# encoder-seed.net
KiCad netlist of a schematic drawn in EAGLE
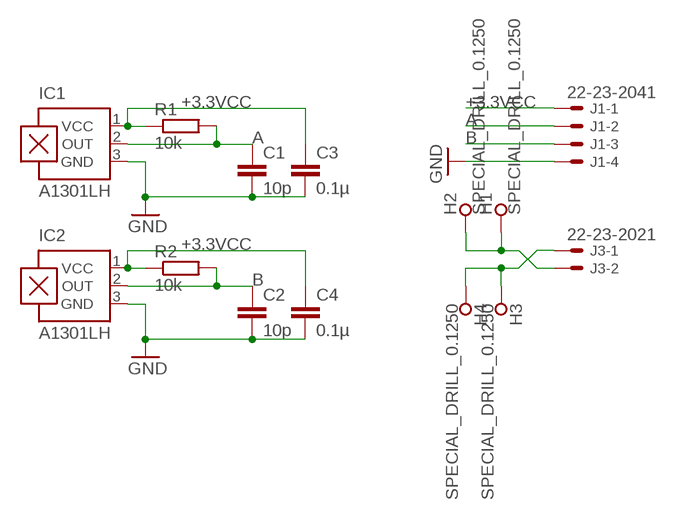
[diagram p0: schematic, sheet 1]

(export (version "E")
  (design (tool "Eeschema 10.0.6"))
  (components
    (comp (ref "C1")
      (value "10p")
      (footprint "eagle-import:C0805")
      (libsource (lib "eagle-import") (part "C-EUC0805"))
    )
    (comp (ref "C2")
      (value "10p")
      (footprint "eagle-import:C0805")
      (libsource (lib "eagle-import") (part "C-EUC0805"))
    )
    (comp (ref "C3")
      (value "0.1µ")
      (footprint "eagle-import:C0805")
      (libsource (lib "eagle-import") (part "C-EUC0805"))
    )
    (comp (ref "C4")
      (value "0.1µ")
      (footprint "eagle-import:C0805")
      (libsource (lib "eagle-import") (part "C-EUC0805"))
    )
    (comp (ref "H1")
      (value "SPECIAL_DRILL_0.1250")
      (footprint "eagle-import:PAD_0.1250")
      (libsource (lib "eagle-import") (part "SPECIAL_DRILL_0.1250"))
    )
    (comp (ref "H2")
      (value "SPECIAL_DRILL_0.1250")
      (footprint "eagle-import:PAD_0.1250")
      (libsource (lib "eagle-import") (part "SPECIAL_DRILL_0.1250"))
    )
    (comp (ref "H3")
      (value "SPECIAL_DRILL_0.1250")
      (footprint "eagle-import:PAD_0.1250")
      (libsource (lib "eagle-import") (part "SPECIAL_DRILL_0.1250"))
    )
    (comp (ref "H4")
      (value "SPECIAL_DRILL_0.1250")
      (footprint "eagle-import:PAD_0.1250")
      (libsource (lib "eagle-import") (part "SPECIAL_DRILL_0.1250"))
    )
    (comp (ref "IC1")
      (value "A1301LH")
      (footprint "eagle-import:SOT23-W")
      (fields (field (name "MF") "ALLEGRO MICROSYSTEMS, INC.") (field (name "MPN") "A1301ELHLT-T"))
      (libsource (lib "eagle-import") (part "A13?LH01"))
    )
    (comp (ref "IC2")
      (value "A1301LH")
      (footprint "eagle-import:SOT23-W")
      (fields (field (name "MF") "ALLEGRO MICROSYSTEMS, INC.") (field (name "MPN") "A1301ELHLT-T"))
      (libsource (lib "eagle-import") (part "A13?LH01"))
    )
    (comp (ref "J1")
      (value "22-23-2041")
      (footprint "eagle-import:22-23-2041")
      (fields (field (name "MF") "MOLEX"))
      (libsource (lib "eagle-import") (part "22-23-2041"))
    )
    (comp (ref "J3")
      (value "22-23-2021")
      (footprint "eagle-import:22-23-2021")
      (fields (field (name "MF") "MOLEX"))
      (libsource (lib "eagle-import") (part "22-23-2021"))
    )
    (comp (ref "R1")
      (value "10k")
      (footprint "eagle-import:R0805")
      (libsource (lib "eagle-import") (part "R-EU_R0805"))
    )
    (comp (ref "R2")
      (value "10k")
      (footprint "eagle-import:R0805")
      (libsource (lib "eagle-import") (part "R-EU_R0805"))
    )
  )
  (nets
    (net (code "1") (name "/+3.3VCC") (class "Default")
      (node (ref "C3") (pin "1") (pinfunction "1_1") (pintype "passive"))
      (node (ref "C4") (pin "1") (pinfunction "1_1") (pintype "passive"))
      (node (ref "IC1") (pin "1") (pinfunction "VCC_1") (pintype "power_in"))
      (node (ref "IC2") (pin "1") (pinfunction "VCC_1") (pintype "power_in"))
      (node (ref "J1") (pin "1") (pinfunction "S_1") (pintype "passive"))
      (node (ref "R1") (pin "1") (pinfunction "1_1") (pintype "passive"))
      (node (ref "R2") (pin "1") (pinfunction "1_1") (pintype "passive"))
    )
    (net (code "2") (name "/A") (class "Default")
      (node (ref "C1") (pin "1") (pinfunction "1_1") (pintype "passive"))
      (node (ref "IC1") (pin "2") (pinfunction "OUT_2") (pintype "output"))
      (node (ref "J1") (pin "2") (pinfunction "S_2") (pintype "passive"))
      (node (ref "R1") (pin "2") (pinfunction "2_2") (pintype "passive"))
    )
    (net (code "3") (name "/B") (class "Default")
      (node (ref "C2") (pin "1") (pinfunction "1_1") (pintype "passive"))
      (node (ref "IC2") (pin "2") (pinfunction "OUT_2") (pintype "output"))
      (node (ref "J1") (pin "3") (pinfunction "S_3") (pintype "passive"))
      (node (ref "R2") (pin "2") (pinfunction "2_2") (pintype "passive"))
    )
    (net (code "4") (name "GND") (class "Default")
      (node (ref "C1") (pin "2") (pinfunction "2_2") (pintype "passive"))
      (node (ref "C2") (pin "2") (pinfunction "2_2") (pintype "passive"))
      (node (ref "C3") (pin "2") (pinfunction "2_2") (pintype "passive"))
      (node (ref "C4") (pin "2") (pinfunction "2_2") (pintype "passive"))
      (node (ref "IC1") (pin "3") (pinfunction "GND_3") (pintype "power_in"))
      (node (ref "IC2") (pin "3") (pinfunction "GND_3") (pintype "power_in"))
      (node (ref "J1") (pin "4") (pinfunction "S_4") (pintype "passive"))
    )
    (net (code "5") (name "Net-(J3A-S)") (class "Default")
      (node (ref "H3") (pin "1") (pinfunction "1_1") (pintype "passive"))
      (node (ref "H4") (pin "1") (pinfunction "1_1") (pintype "passive"))
      (node (ref "J3") (pin "1") (pinfunction "S_1") (pintype "passive"))
    )
    (net (code "6") (name "Net-(J3B-S)") (class "Default")
      (node (ref "H1") (pin "1") (pinfunction "1_1") (pintype "passive"))
      (node (ref "H2") (pin "1") (pinfunction "1_1") (pintype "passive"))
      (node (ref "J3") (pin "2") (pinfunction "S_2") (pintype "passive"))
    )
  )
)
